# bl_dora2.net
KiCad netlist of a schematic drawn in EAGLE
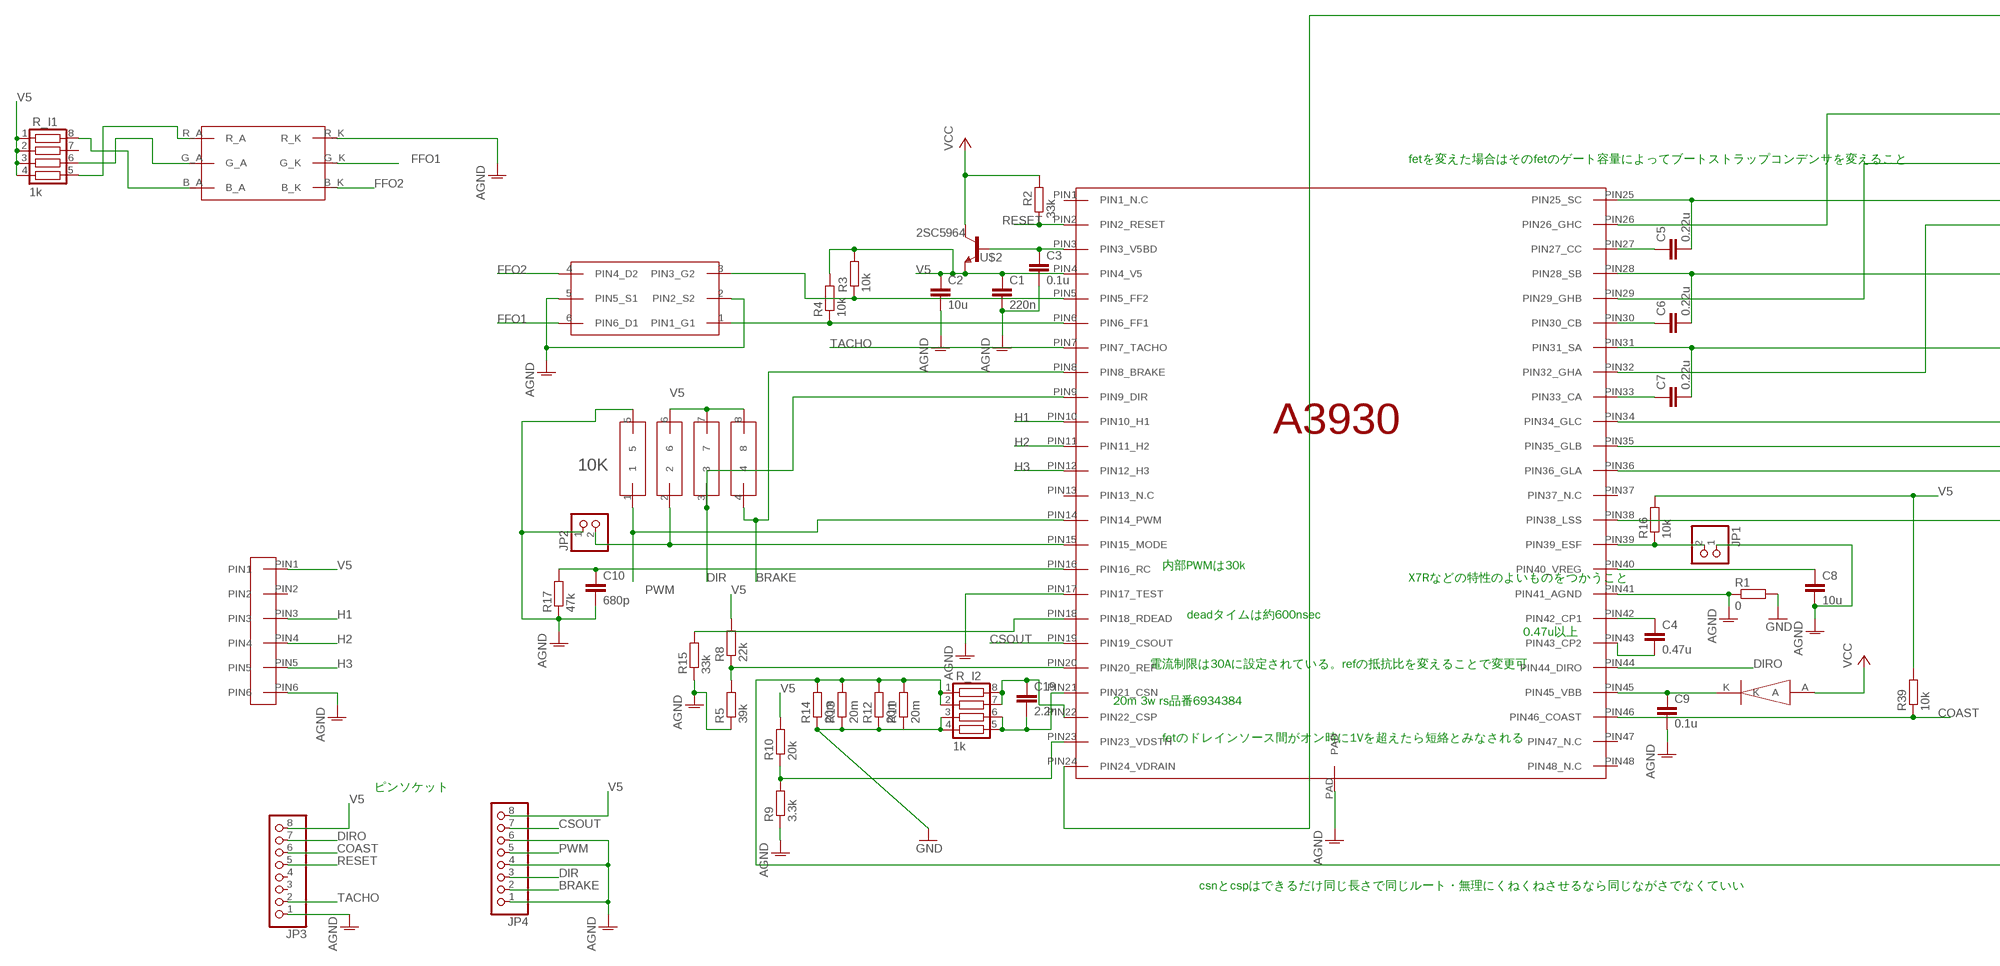
[diagram p0: schematic, sheet 1, part 1 of 2]
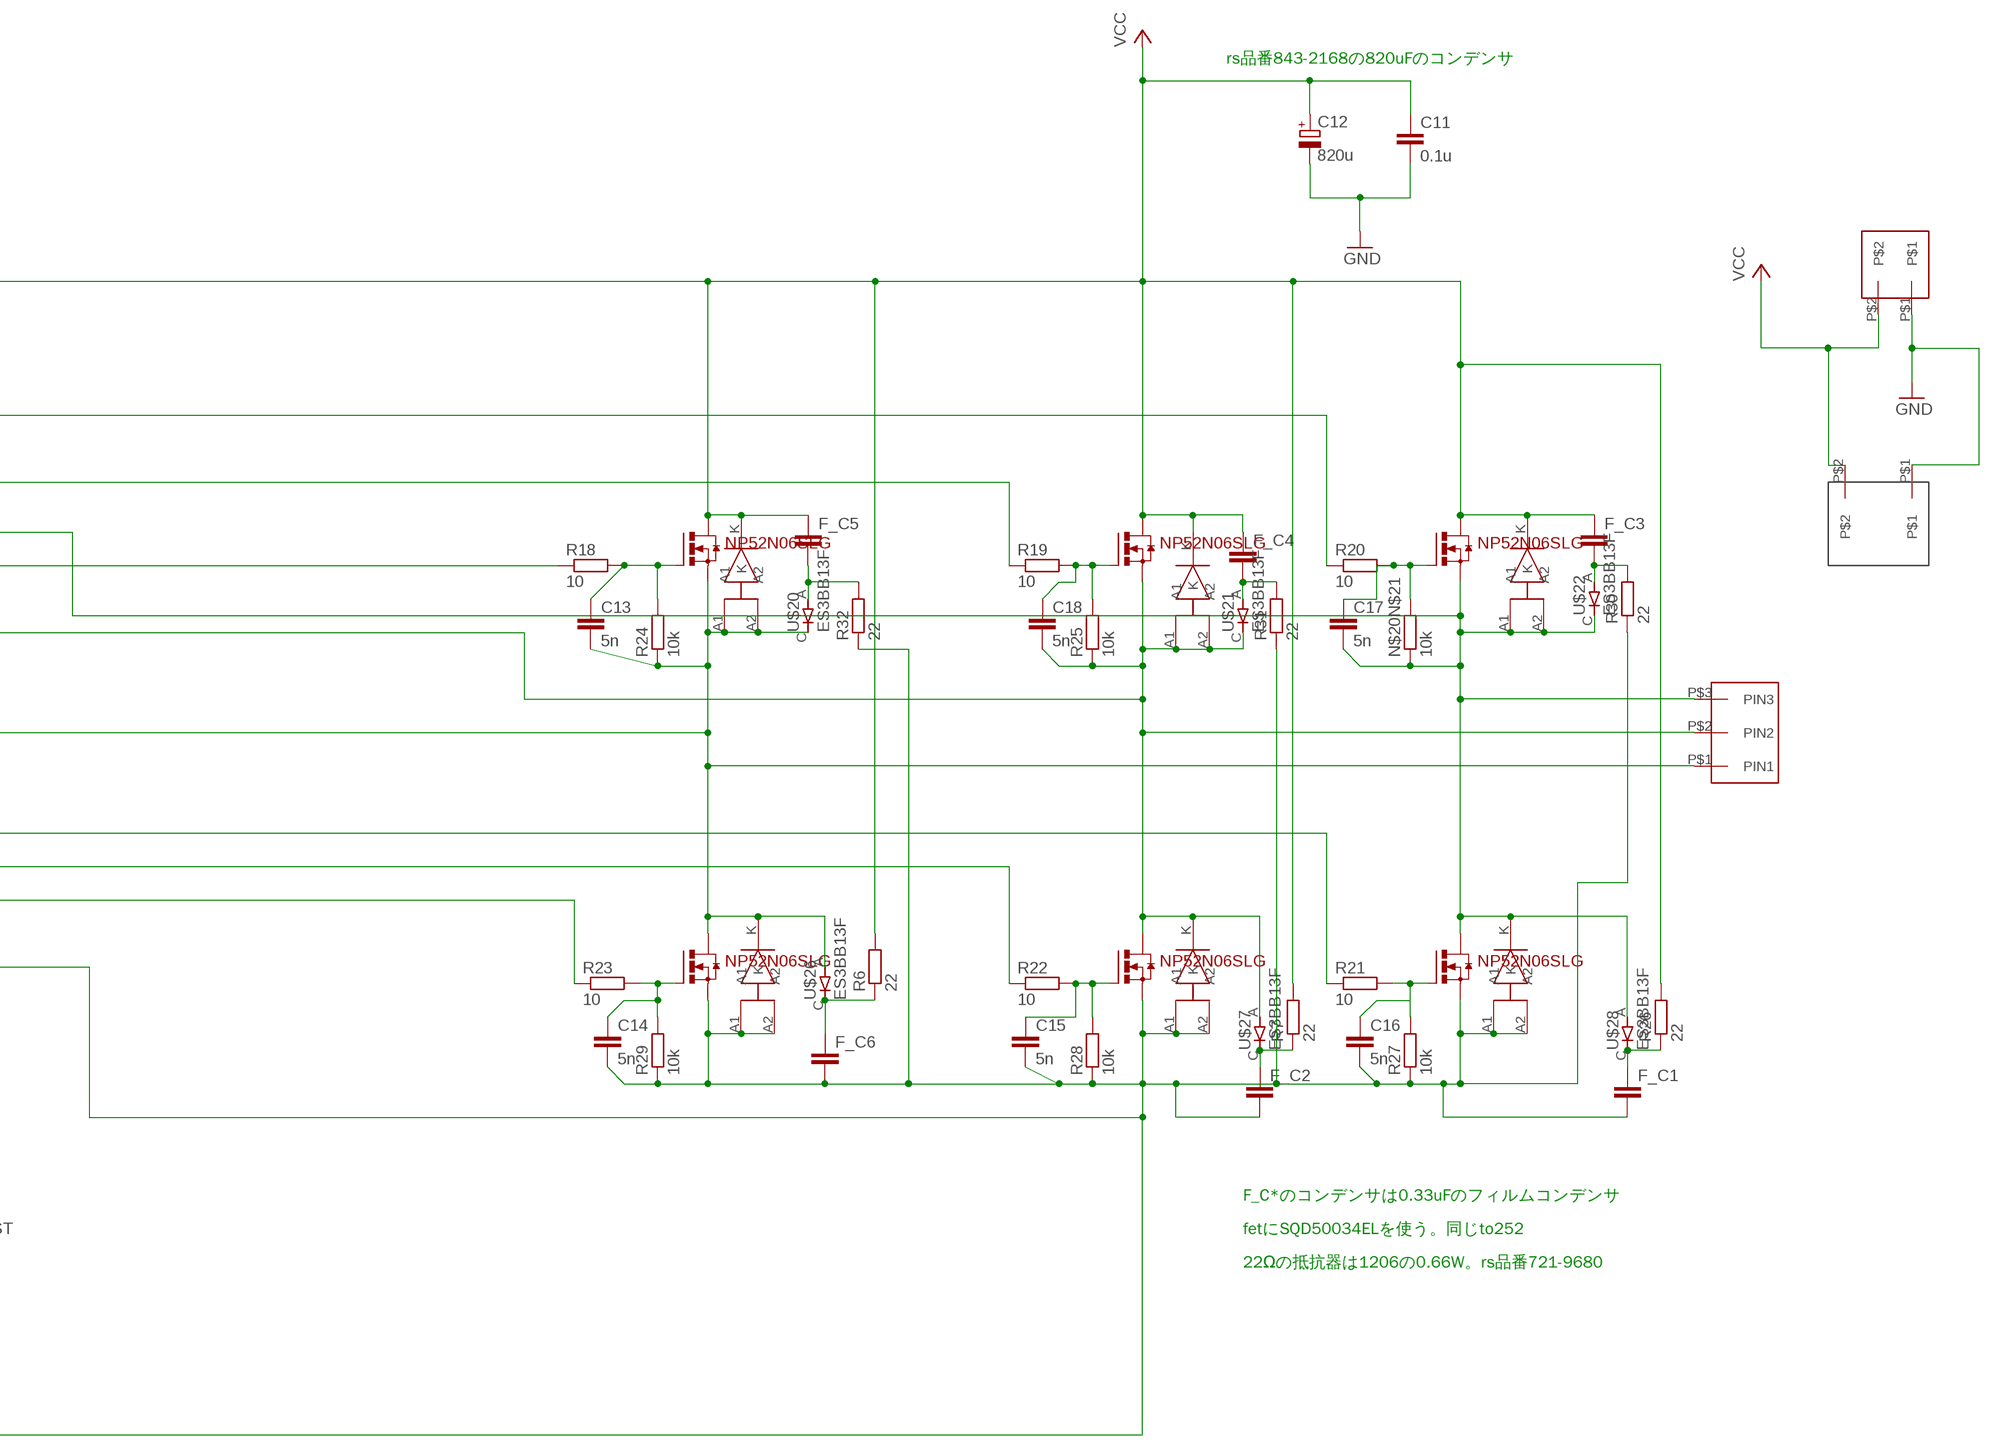
[diagram p1: schematic, sheet 1, part 2 of 2]

(export (version "E")
  (design (tool "Eeschema 10.0.6"))
  (components
    (comp (ref "C1")
      (value "220n")
      (footprint "eagle-import:C2012")
      (libsource (lib "eagle-import") (part "C-EUC2012"))
    )
    (comp (ref "C2")
      (value "10u")
      (footprint "eagle-import:C2012")
      (libsource (lib "eagle-import") (part "C-EUC2012"))
    )
    (comp (ref "C3")
      (value "0.1u")
      (footprint "eagle-import:C2012")
      (libsource (lib "eagle-import") (part "C-EUC2012"))
    )
    (comp (ref "C4")
      (value "0.47u")
      (footprint "eagle-import:C2012")
      (libsource (lib "eagle-import") (part "C-EUC2012"))
    )
    (comp (ref "C5")
      (value "0.22u")
      (footprint "eagle-import:C2012")
      (libsource (lib "eagle-import") (part "C-EUC2012"))
    )
    (comp (ref "C6")
      (value "0.22u")
      (footprint "eagle-import:C2012")
      (libsource (lib "eagle-import") (part "C-EUC2012"))
    )
    (comp (ref "C7")
      (value "0.22u")
      (footprint "eagle-import:C2012")
      (libsource (lib "eagle-import") (part "C-EUC2012"))
    )
    (comp (ref "C8")
      (value "10u")
      (footprint "eagle-import:C2012")
      (libsource (lib "eagle-import") (part "C-EUC2012"))
    )
    (comp (ref "C9")
      (value "0.1u")
      (footprint "eagle-import:C2012")
      (libsource (lib "eagle-import") (part "C-EUC2012"))
    )
    (comp (ref "C10")
      (value "680p")
      (footprint "eagle-import:C2012")
      (libsource (lib "eagle-import") (part "C-EUC2012"))
    )
    (comp (ref "C11")
      (value "0.1u")
      (footprint "eagle-import:C2012")
      (libsource (lib "eagle-import") (part "C-EUC2012"))
    )
    (comp (ref "C12")
      (value "820u")
      (footprint "eagle-import:153CLV-1012")
      (libsource (lib "eagle-import") (part "CPOL-EU153CLV-1012"))
    )
    (comp (ref "C13")
      (value "5n")
      (footprint "eagle-import:C2012")
      (libsource (lib "eagle-import") (part "C-EUC2012"))
    )
    (comp (ref "C14")
      (value "5n")
      (footprint "eagle-import:C2012")
      (libsource (lib "eagle-import") (part "C-EUC2012"))
    )
    (comp (ref "C15")
      (value "5n")
      (footprint "eagle-import:C2012")
      (libsource (lib "eagle-import") (part "C-EUC2012"))
    )
    (comp (ref "C16")
      (value "5n")
      (footprint "eagle-import:C2012")
      (libsource (lib "eagle-import") (part "C-EUC2012"))
    )
    (comp (ref "C17")
      (value "5n")
      (footprint "eagle-import:C2012")
      (libsource (lib "eagle-import") (part "C-EUC2012"))
    )
    (comp (ref "C18")
      (value "5n")
      (footprint "eagle-import:C2012")
      (libsource (lib "eagle-import") (part "C-EUC2012"))
    )
    (comp (ref "C19")
      (value "2.2n")
      (footprint "eagle-import:C1608")
      (libsource (lib "eagle-import") (part "C-EUC1608"))
    )
    (comp (ref "F_C1")
      (value "FIL_CAPA")
      (footprint "eagle-import:FIL_CAPA")
      (libsource (lib "eagle-import") (part "FIL_CAPA"))
    )
    (comp (ref "F_C2")
      (value "FIL_CAPA")
      (footprint "eagle-import:FIL_CAPA")
      (libsource (lib "eagle-import") (part "FIL_CAPA"))
    )
    (comp (ref "F_C3")
      (value "FIL_CAPA")
      (footprint "eagle-import:FIL_CAPA")
      (libsource (lib "eagle-import") (part "FIL_CAPA"))
    )
    (comp (ref "F_C4")
      (value "FIL_CAPA")
      (footprint "eagle-import:FIL_CAPA")
      (libsource (lib "eagle-import") (part "FIL_CAPA"))
    )
    (comp (ref "F_C5")
      (value "FIL_CAPA")
      (footprint "eagle-import:FIL_CAPA")
      (libsource (lib "eagle-import") (part "FIL_CAPA"))
    )
    (comp (ref "F_C6")
      (value "FIL_CAPA")
      (footprint "eagle-import:FIL_CAPA")
      (libsource (lib "eagle-import") (part "FIL_CAPA"))
    )
    (comp (ref "JP1")
      (value "PINHD-1X2")
      (footprint "eagle-import:1X02")
      (libsource (lib "eagle-import") (part "PINHD-1X2"))
    )
    (comp (ref "JP2")
      (value "PINHD-1X2")
      (footprint "eagle-import:1X02")
      (libsource (lib "eagle-import") (part "PINHD-1X2"))
    )
    (comp (ref "JP3")
      (value "PINHD-1X8")
      (footprint "eagle-import:1X08")
      (libsource (lib "eagle-import") (part "PINHD-1X8"))
    )
    (comp (ref "JP4")
      (value "PINHD-1X8")
      (footprint "eagle-import:1X08")
      (libsource (lib "eagle-import") (part "PINHD-1X8"))
    )
    (comp (ref "N$20N$21")
      (value "10k")
      (footprint "eagle-import:M2012")
      (libsource (lib "eagle-import") (part "R-EU_M2012"))
    )
    (comp (ref "R1")
      (value "0")
      (footprint "eagle-import:M2012")
      (libsource (lib "eagle-import") (part "R-EU_M2012"))
    )
    (comp (ref "R2")
      (value "33k")
      (footprint "eagle-import:M2012")
      (libsource (lib "eagle-import") (part "R-EU_M2012"))
    )
    (comp (ref "R3")
      (value "10k")
      (footprint "eagle-import:M2012")
      (libsource (lib "eagle-import") (part "R-EU_M2012"))
    )
    (comp (ref "R4")
      (value "10k")
      (footprint "eagle-import:M2012")
      (libsource (lib "eagle-import") (part "R-EU_M2012"))
    )
    (comp (ref "R5")
      (value "39k")
      (footprint "eagle-import:M2012")
      (libsource (lib "eagle-import") (part "R-EU_M2012"))
    )
    (comp (ref "R6")
      (value "22")
      (footprint "eagle-import:R1206")
      (libsource (lib "eagle-import") (part "R-EU_R1206"))
    )
    (comp (ref "R7")
      (value "22")
      (footprint "eagle-import:R1206")
      (libsource (lib "eagle-import") (part "R-EU_R1206"))
    )
    (comp (ref "R8")
      (value "22k")
      (footprint "eagle-import:M2012")
      (libsource (lib "eagle-import") (part "R-EU_M2012"))
    )
    (comp (ref "R9")
      (value "3.3k")
      (footprint "eagle-import:M2012")
      (libsource (lib "eagle-import") (part "R-EU_M2012"))
    )
    (comp (ref "R10")
      (value "20k")
      (footprint "eagle-import:M2012")
      (libsource (lib "eagle-import") (part "R-EU_M2012"))
    )
    (comp (ref "R11")
      (value "20m")
      (footprint "eagle-import:R2512")
      (libsource (lib "eagle-import") (part "R-EU_R2512"))
    )
    (comp (ref "R12")
      (value "20m")
      (footprint "eagle-import:R2512")
      (libsource (lib "eagle-import") (part "R-EU_R2512"))
    )
    (comp (ref "R13")
      (value "20m")
      (footprint "eagle-import:R2512")
      (libsource (lib "eagle-import") (part "R-EU_R2512"))
    )
    (comp (ref "R14")
      (value "20m")
      (footprint "eagle-import:R2512")
      (libsource (lib "eagle-import") (part "R-EU_R2512"))
    )
    (comp (ref "R15")
      (value "33k")
      (footprint "eagle-import:M2012")
      (libsource (lib "eagle-import") (part "R-EU_M2012"))
    )
    (comp (ref "R16")
      (value "10k")
      (footprint "eagle-import:M2012")
      (libsource (lib "eagle-import") (part "R-EU_M2012"))
    )
    (comp (ref "R17")
      (value "47k")
      (footprint "eagle-import:M2012")
      (libsource (lib "eagle-import") (part "R-EU_M2012"))
    )
    (comp (ref "R18")
      (value "10")
      (footprint "eagle-import:M2012")
      (libsource (lib "eagle-import") (part "R-EU_M2012"))
    )
    (comp (ref "R19")
      (value "10")
      (footprint "eagle-import:M2012")
      (libsource (lib "eagle-import") (part "R-EU_M2012"))
    )
    (comp (ref "R20")
      (value "10")
      (footprint "eagle-import:M2012")
      (libsource (lib "eagle-import") (part "R-EU_M2012"))
    )
    (comp (ref "R21")
      (value "10")
      (footprint "eagle-import:M2012")
      (libsource (lib "eagle-import") (part "R-EU_M2012"))
    )
    (comp (ref "R22")
      (value "10")
      (footprint "eagle-import:M2012")
      (libsource (lib "eagle-import") (part "R-EU_M2012"))
    )
    (comp (ref "R23")
      (value "10")
      (footprint "eagle-import:M2012")
      (libsource (lib "eagle-import") (part "R-EU_M2012"))
    )
    (comp (ref "R24")
      (value "10k")
      (footprint "eagle-import:M2012")
      (libsource (lib "eagle-import") (part "R-EU_M2012"))
    )
    (comp (ref "R25")
      (value "10k")
      (footprint "eagle-import:M2012")
      (libsource (lib "eagle-import") (part "R-EU_M2012"))
    )
    (comp (ref "R26")
      (value "22")
      (footprint "eagle-import:R1206")
      (libsource (lib "eagle-import") (part "R-EU_R1206"))
    )
    (comp (ref "R27")
      (value "10k")
      (footprint "eagle-import:M2012")
      (libsource (lib "eagle-import") (part "R-EU_M2012"))
    )
    (comp (ref "R28")
      (value "10k")
      (footprint "eagle-import:M2012")
      (libsource (lib "eagle-import") (part "R-EU_M2012"))
    )
    (comp (ref "R29")
      (value "10k")
      (footprint "eagle-import:M2012")
      (libsource (lib "eagle-import") (part "R-EU_M2012"))
    )
    (comp (ref "R30")
      (value "22")
      (footprint "eagle-import:R1206")
      (libsource (lib "eagle-import") (part "R-EU_R1206"))
    )
    (comp (ref "R31")
      (value "22")
      (footprint "eagle-import:R1206")
      (libsource (lib "eagle-import") (part "R-EU_R1206"))
    )
    (comp (ref "R32")
      (value "22")
      (footprint "eagle-import:R1206")
      (libsource (lib "eagle-import") (part "R-EU_R1206"))
    )
    (comp (ref "R39")
      (value "10k")
      (footprint "eagle-import:M2012")
      (libsource (lib "eagle-import") (part "R-EU_M2012"))
    )
    (comp (ref "R_I1")
      (value "1k")
      (footprint "eagle-import:0603X4RESISTOR")
      (libsource (lib "eagle-import") (part "0603X4RESISTOR"))
    )
    (comp (ref "R_I2")
      (value "1k")
      (footprint "eagle-import:0603X4RESISTOR")
      (libsource (lib "eagle-import") (part "R_SHUGOU"))
    )
    (comp (ref "U$1")
      (value "A3930")
      (footprint "eagle-import:A3930")
      (libsource (lib "eagle-import") (part "A3930"))
    )
    (comp (ref "U$2")
      (value "2SC5964")
      (footprint "eagle-import:2SC5964")
      (libsource (lib "eagle-import") (part "2SC5964"))
    )
    (comp (ref "U$3")
      (value "SSOT6_FET")
      (footprint "eagle-import:SSOT6_FET")
      (libsource (lib "eagle-import") (part "SSOT6_FET"))
    )
    (comp (ref "U$4")
      (value "RGB_LED")
      (footprint "eagle-import:RGB_LED")
      (libsource (lib "eagle-import") (part "RGB_LED"))
    )
    (comp (ref "U$5")
      (value "10K")
      (footprint "eagle-import:1005X4RESISTOR")
      (libsource (lib "eagle-import") (part "1005X4RESISTOR"))
    )
    (comp (ref "U$6")
      (value "SMD_DAIOD")
      (footprint "eagle-import:SMD_DAIOD")
      (libsource (lib "eagle-import") (part "SMD_DAIOD"))
    )
    (comp (ref "U$7")
      (value "NP52N06SLG")
      (footprint "eagle-import:NP52N06SLG")
      (libsource (lib "eagle-import") (part "NP52N06SLG"))
    )
    (comp (ref "U$8")
      (value "NP52N06SLG")
      (footprint "eagle-import:NP52N06SLG")
      (libsource (lib "eagle-import") (part "NP52N06SLG"))
    )
    (comp (ref "U$9")
      (value "NP52N06SLG")
      (footprint "eagle-import:NP52N06SLG")
      (libsource (lib "eagle-import") (part "NP52N06SLG"))
    )
    (comp (ref "U$10")
      (value "NP52N06SLG")
      (footprint "eagle-import:NP52N06SLG")
      (libsource (lib "eagle-import") (part "NP52N06SLG"))
    )
    (comp (ref "U$11")
      (value "NP52N06SLG")
      (footprint "eagle-import:NP52N06SLG")
      (libsource (lib "eagle-import") (part "NP52N06SLG"))
    )
    (comp (ref "U$12")
      (value "NP52N06SLG")
      (footprint "eagle-import:NP52N06SLG")
      (libsource (lib "eagle-import") (part "NP52N06SLG"))
    )
    (comp (ref "U$13")
      (value "SBR10M100P5Q")
      (footprint "eagle-import:SBR10M100P5Q")
      (libsource (lib "eagle-import") (part "SBR10M100P5Q"))
    )
    (comp (ref "U$14")
      (value "SBR10M100P5Q")
      (footprint "eagle-import:SBR10M100P5Q")
      (libsource (lib "eagle-import") (part "SBR10M100P5Q"))
    )
    (comp (ref "U$15")
      (value "SBR10M100P5Q")
      (footprint "eagle-import:SBR10M100P5Q")
      (libsource (lib "eagle-import") (part "SBR10M100P5Q"))
    )
    (comp (ref "U$16")
      (value "SBR10M100P5Q")
      (footprint "eagle-import:SBR10M100P5Q")
      (libsource (lib "eagle-import") (part "SBR10M100P5Q"))
    )
    (comp (ref "U$17")
      (value "SBR10M100P5Q")
      (footprint "eagle-import:SBR10M100P5Q")
      (libsource (lib "eagle-import") (part "SBR10M100P5Q"))
    )
    (comp (ref "U$18")
      (value "SBR10M100P5Q")
      (footprint "eagle-import:SBR10M100P5Q")
      (libsource (lib "eagle-import") (part "SBR10M100P5Q"))
    )
    (comp (ref "U$19")
      (value "XH_2P")
      (footprint "eagle-import:XH_2P")
      (libsource (lib "eagle-import") (part "XH_2P"))
    )
    (comp (ref "U$20")
      (value "ES3BB13F")
      (footprint "eagle-import:ES3BB13F")
      (libsource (lib "eagle-import") (part "ES3BB13F"))
    )
    (comp (ref "U$21")
      (value "ES3BB13F")
      (footprint "eagle-import:ES3BB13F")
      (libsource (lib "eagle-import") (part "ES3BB13F"))
    )
    (comp (ref "U$22")
      (value "ES3BB13F")
      (footprint "eagle-import:ES3BB13F")
      (libsource (lib "eagle-import") (part "ES3BB13F"))
    )
    (comp (ref "U$23")
      (value "ZH_6P_L")
      (footprint "eagle-import:ZH_6P_L")
      (libsource (lib "eagle-import") (part "ZH_6P_L"))
    )
    (comp (ref "U$24")
      (value "XT60")
      (footprint "eagle-import:XT60")
      (libsource (lib "eagle-import") (part "XT60"))
    )
    (comp (ref "U$25")
      (value "VL_3P")
      (footprint "eagle-import:VL_3P")
      (libsource (lib "eagle-import") (part "VL_3P"))
    )
    (comp (ref "U$26")
      (value "ES3BB13F")
      (footprint "eagle-import:ES3BB13F")
      (libsource (lib "eagle-import") (part "ES3BB13F"))
    )
    (comp (ref "U$27")
      (value "ES3BB13F")
      (footprint "eagle-import:ES3BB13F")
      (libsource (lib "eagle-import") (part "ES3BB13F"))
    )
    (comp (ref "U$28")
      (value "ES3BB13F")
      (footprint "eagle-import:ES3BB13F")
      (libsource (lib "eagle-import") (part "ES3BB13F"))
    )
  )
  (nets
    (net (code "1") (name "/BRAKE") (class "Default")
      (node (ref "JP4") (pin "2") (pinfunction "2_2") (pintype "passive"))
      (node (ref "U$1") (pin "PIN8") (pinfunction "PIN8_BRAKE_PIN8") (pintype "bidirectional"))
      (node (ref "U$5") (pin "4") (pinfunction "4_4") (pintype "bidirectional"))
    )
    (net (code "2") (name "/COAST") (class "Default")
      (node (ref "JP3") (pin "6") (pinfunction "6_6") (pintype "passive"))
      (node (ref "R39") (pin "1") (pinfunction "1_1") (pintype "passive"))
      (node (ref "U$1") (pin "PIN46") (pinfunction "PIN46_COAST_PIN46") (pintype "bidirectional"))
    )
    (net (code "3") (name "/CSOUT") (class "Default")
      (node (ref "JP4") (pin "7") (pinfunction "7_7") (pintype "passive"))
      (node (ref "U$1") (pin "PIN19") (pinfunction "PIN19_CSOUT_PIN19") (pintype "bidirectional"))
    )
    (net (code "4") (name "/DIR") (class "Default")
      (node (ref "JP4") (pin "3") (pinfunction "3_3") (pintype "passive"))
      (node (ref "U$1") (pin "PIN9") (pinfunction "PIN9_DIR_PIN9") (pintype "bidirectional"))
      (node (ref "U$5") (pin "3") (pinfunction "3_3") (pintype "bidirectional"))
    )
    (net (code "5") (name "/DIRO") (class "Default")
      (node (ref "JP3") (pin "7") (pinfunction "7_7") (pintype "passive"))
      (node (ref "U$1") (pin "PIN44") (pinfunction "PIN44_DIRO_PIN44") (pintype "bidirectional"))
    )
    (net (code "6") (name "/FFO1") (class "Default")
      (node (ref "U$3") (pin "6") (pinfunction "PIN6_D1_6") (pintype "bidirectional"))
      (node (ref "U$4") (pin "G_K") (pinfunction "G_K_G_K") (pintype "bidirectional"))
    )
    (net (code "7") (name "/FFO2") (class "Default")
      (node (ref "U$3") (pin "4") (pinfunction "PIN4_D2_4") (pintype "bidirectional"))
      (node (ref "U$4") (pin "B_K") (pinfunction "B_K_B_K") (pintype "bidirectional"))
    )
    (net (code "8") (name "/H1") (class "Default")
      (node (ref "U$1") (pin "PIN10") (pinfunction "PIN10_H1_PIN10") (pintype "bidirectional"))
      (node (ref "U$23") (pin "PIN3") (pinfunction "PIN3_PIN3") (pintype "bidirectional"))
    )
    (net (code "9") (name "/H2") (class "Default")
      (node (ref "U$1") (pin "PIN11") (pinfunction "PIN11_H2_PIN11") (pintype "bidirectional"))
      (node (ref "U$23") (pin "PIN4") (pinfunction "PIN4_PIN4") (pintype "bidirectional"))
    )
    (net (code "10") (name "/H3") (class "Default")
      (node (ref "U$1") (pin "PIN12") (pinfunction "PIN12_H3_PIN12") (pintype "bidirectional"))
      (node (ref "U$23") (pin "PIN5") (pinfunction "PIN5_PIN5") (pintype "bidirectional"))
    )
    (net (code "11") (name "/PWM") (class "Default")
      (node (ref "JP4") (pin "5") (pinfunction "5_5") (pintype "passive"))
      (node (ref "U$1") (pin "PIN14") (pinfunction "PIN14_PWM_PIN14") (pintype "bidirectional"))
      (node (ref "U$5") (pin "1") (pinfunction "1_1") (pintype "bidirectional"))
    )
    (net (code "12") (name "/RESET") (class "Default")
      (node (ref "JP3") (pin "5") (pinfunction "5_5") (pintype "passive"))
      (node (ref "R2") (pin "1") (pinfunction "1_1") (pintype "passive"))
      (node (ref "U$1") (pin "PIN2") (pinfunction "PIN2_RESET_PIN2") (pintype "bidirectional"))
    )
    (net (code "13") (name "/TACHO") (class "Default")
      (node (ref "JP3") (pin "2") (pinfunction "2_2") (pintype "passive"))
      (node (ref "U$1") (pin "PIN7") (pinfunction "PIN7_TACHO_PIN7") (pintype "bidirectional"))
    )
    (net (code "14") (name "/V5") (class "Default")
      (node (ref "C1") (pin "1") (pinfunction "1_1") (pintype "passive"))
      (node (ref "C2") (pin "1") (pinfunction "1_1") (pintype "passive"))
      (node (ref "JP3") (pin "8") (pinfunction "8_8") (pintype "passive"))
      (node (ref "JP4") (pin "8") (pinfunction "8_8") (pintype "passive"))
      (node (ref "R10") (pin "2") (pinfunction "2_2") (pintype "passive"))
      (node (ref "R16") (pin "2") (pinfunction "2_2") (pintype "passive"))
      (node (ref "R3") (pin "2") (pinfunction "2_2") (pintype "passive"))
      (node (ref "R39") (pin "2") (pinfunction "2_2") (pintype "passive"))
      (node (ref "R4") (pin "2") (pinfunction "2_2") (pintype "passive"))
      (node (ref "R8") (pin "2") (pinfunction "2_2") (pintype "passive"))
      (node (ref "R_I1") (pin "1") (pinfunction "1_1") (pintype "passive"))
      (node (ref "R_I1") (pin "2") (pinfunction "2_2") (pintype "passive"))
      (node (ref "R_I1") (pin "3") (pinfunction "3_3") (pintype "passive"))
      (node (ref "R_I1") (pin "4") (pinfunction "4_4") (pintype "passive"))
      (node (ref "U$1") (pin "PIN4") (pinfunction "PIN4_V5_PIN4") (pintype "bidirectional"))
      (node (ref "U$2") (pin "E") (pinfunction "E_E") (pintype "passive"))
      (node (ref "U$23") (pin "PIN1") (pinfunction "PIN1_PIN1") (pintype "bidirectional"))
      (node (ref "U$5") (pin "6") (pinfunction "6_6") (pintype "bidirectional"))
      (node (ref "U$5") (pin "7") (pinfunction "7_7") (pintype "bidirectional"))
      (node (ref "U$5") (pin "8") (pinfunction "8_8") (pintype "bidirectional"))
    )
    (net (code "15") (name "AGND") (class "Default")
      (node (ref "C1") (pin "2") (pinfunction "2_2") (pintype "passive"))
      (node (ref "C10") (pin "2") (pinfunction "2_2") (pintype "passive"))
      (node (ref "C2") (pin "2") (pinfunction "2_2") (pintype "passive"))
      (node (ref "C3") (pin "2") (pinfunction "2_2") (pintype "passive"))
      (node (ref "C8") (pin "2") (pinfunction "2_2") (pintype "passive"))
      (node (ref "C9") (pin "2") (pinfunction "2_2") (pintype "passive"))
      (node (ref "JP1") (pin "1") (pinfunction "1_1") (pintype "passive"))
      (node (ref "JP2") (pin "1") (pinfunction "1_1") (pintype "passive"))
      (node (ref "JP3") (pin "1") (pinfunction "1_1") (pintype "passive"))
      (node (ref "JP4") (pin "1") (pinfunction "1_1") (pintype "passive"))
      (node (ref "JP4") (pin "4") (pinfunction "4_4") (pintype "passive"))
      (node (ref "JP4") (pin "6") (pinfunction "6_6") (pintype "passive"))
      (node (ref "R1") (pin "1") (pinfunction "1_1") (pintype "passive"))
      (node (ref "R15") (pin "1") (pinfunction "1_1") (pintype "passive"))
      (node (ref "R17") (pin "1") (pinfunction "1_1") (pintype "passive"))
      (node (ref "R5") (pin "1") (pinfunction "1_1") (pintype "passive"))
      (node (ref "R9") (pin "1") (pinfunction "1_1") (pintype "passive"))
      (node (ref "U$1") (pin "PAD") (pinfunction "PAD_PAD") (pintype "bidirectional"))
      (node (ref "U$1") (pin "PIN17") (pinfunction "PIN17_TEST_PIN17") (pintype "bidirectional"))
      (node (ref "U$1") (pin "PIN41") (pinfunction "PIN41_AGND_PIN41") (pintype "bidirectional"))
      (node (ref "U$23") (pin "PIN6") (pinfunction "PIN6_PIN6") (pintype "bidirectional"))
      (node (ref "U$3") (pin "2") (pinfunction "PIN2_S2_2") (pintype "bidirectional"))
      (node (ref "U$3") (pin "5") (pinfunction "PIN5_S1_5") (pintype "bidirectional"))
      (node (ref "U$4") (pin "R_K") (pinfunction "R_K_R_K") (pintype "bidirectional"))
      (node (ref "U$5") (pin "5") (pinfunction "5_5") (pintype "bidirectional"))
    )
    (net (code "16") (name "GND") (class "Default")
      (node (ref "C11") (pin "2") (pinfunction "2_2") (pintype "passive"))
      (node (ref "C12") (pin "-") (pinfunction "-_-") (pintype "passive"))
      (node (ref "R1") (pin "2") (pinfunction "2_2") (pintype "passive"))
      (node (ref "R11") (pin "1") (pinfunction "1_1") (pintype "passive"))
      (node (ref "R12") (pin "1") (pinfunction "1_1") (pintype "passive"))
      (node (ref "R13") (pin "1") (pinfunction "1_1") (pintype "passive"))
      (node (ref "R14") (pin "1") (pinfunction "1_1") (pintype "passive"))
      (node (ref "R_I2") (pin "3") (pinfunction "3_3") (pintype "passive"))
      (node (ref "R_I2") (pin "4") (pinfunction "4_4") (pintype "passive"))
      (node (ref "U$19") (pin "P$1") (pinfunction "P$1_P$1") (pintype "bidirectional"))
      (node (ref "U$24") (pin "P$1") (pinfunction "P$1_P$1") (pintype "bidirectional"))
    )
    (net (code "17") (name "Net-(C13-Pad1)") (class "Default")
      (node (ref "C13") (pin "1") (pinfunction "1_1") (pintype "passive"))
      (node (ref "R18") (pin "2") (pinfunction "2_2") (pintype "passive"))
      (node (ref "R24") (pin "2") (pinfunction "2_2") (pintype "passive"))
      (node (ref "U$7") (pin "PIN1_G") (pinfunction "PIN1_G_PIN1_G") (pintype "passive"))
    )
    (net (code "18") (name "Net-(C14-Pad1)") (class "Default")
      (node (ref "C14") (pin "1") (pinfunction "1_1") (pintype "passive"))
      (node (ref "R23") (pin "2") (pinfunction "2_2") (pintype "passive"))
      (node (ref "R29") (pin "2") (pinfunction "2_2") (pintype "passive"))
      (node (ref "U$8") (pin "PIN1_G") (pinfunction "PIN1_G_PIN1_G") (pintype "passive"))
    )
    (net (code "19") (name "Net-(C15-Pad1)") (class "Default")
      (node (ref "C15") (pin "1") (pinfunction "1_1") (pintype "passive"))
      (node (ref "R22") (pin "2") (pinfunction "2_2") (pintype "passive"))
      (node (ref "R28") (pin "2") (pinfunction "2_2") (pintype "passive"))
      (node (ref "U$10") (pin "PIN1_G") (pinfunction "PIN1_G_PIN1_G") (pintype "passive"))
    )
    (net (code "20") (name "Net-(C16-Pad1)") (class "Default")
      (node (ref "C16") (pin "1") (pinfunction "1_1") (pintype "passive"))
      (node (ref "R21") (pin "2") (pinfunction "2_2") (pintype "passive"))
      (node (ref "R27") (pin "2") (pinfunction "2_2") (pintype "passive"))
      (node (ref "U$12") (pin "PIN1_G") (pinfunction "PIN1_G_PIN1_G") (pintype "passive"))
    )
    (net (code "21") (name "Net-(C17-Pad1)") (class "Default")
      (node (ref "C17") (pin "1") (pinfunction "1_1") (pintype "passive"))
      (node (ref "N$20N$21") (pin "2") (pinfunction "2_2") (pintype "passive"))
      (node (ref "R20") (pin "2") (pinfunction "2_2") (pintype "passive"))
      (node (ref "U$11") (pin "PIN1_G") (pinfunction "PIN1_G_PIN1_G") (pintype "passive"))
    )
    (net (code "22") (name "Net-(C18-Pad1)") (class "Default")
      (node (ref "C18") (pin "1") (pinfunction "1_1") (pintype "passive"))
      (node (ref "R19") (pin "2") (pinfunction "2_2") (pintype "passive"))
      (node (ref "R25") (pin "2") (pinfunction "2_2") (pintype "passive"))
      (node (ref "U$9") (pin "PIN1_G") (pinfunction "PIN1_G_PIN1_G") (pintype "passive"))
    )
    (net (code "23") (name "Net-(F_C1-1)") (class "Default")
      (node (ref "F_C1") (pin "P$1") (pinfunction "1_P$1") (pintype "passive"))
      (node (ref "R26") (pin "1") (pinfunction "1_1") (pintype "passive"))
      (node (ref "U$28") (pin "C") (pinfunction "C_C") (pintype "passive"))
    )
    (net (code "24") (name "Net-(F_C1-2)") (class "Default")
      (node (ref "C14") (pin "2") (pinfunction "2_2") (pintype "passive"))
      (node (ref "C15") (pin "2") (pinfunction "2_2") (pintype "passive"))
      (node (ref "C16") (pin "2") (pinfunction "2_2") (pintype "passive"))
      (node (ref "F_C1") (pin "P$2") (pinfunction "2_P$2") (pintype "passive"))
      (node (ref "F_C2") (pin "P$2") (pinfunction "2_P$2") (pintype "passive"))
      (node (ref "F_C6") (pin "P$2") (pinfunction "2_P$2") (pintype "passive"))
      (node (ref "R11") (pin "2") (pinfunction "2_2") (pintype "passive"))
      (node (ref "R12") (pin "2") (pinfunction "2_2") (pintype "passive"))
      (node (ref "R13") (pin "2") (pinfunction "2_2") (pintype "passive"))
      (node (ref "R14") (pin "2") (pinfunction "2_2") (pintype "passive"))
      (node (ref "R27") (pin "1") (pinfunction "1_1") (pintype "passive"))
      (node (ref "R28") (pin "1") (pinfunction "1_1") (pintype "passive"))
      (node (ref "R29") (pin "1") (pinfunction "1_1") (pintype "passive"))
      (node (ref "R30") (pin "1") (pinfunction "1_1") (pintype "passive"))
      (node (ref "R31") (pin "1") (pinfunction "1_1") (pintype "passive"))
      (node (ref "R32") (pin "1") (pinfunction "1_1") (pintype "passive"))
      (node (ref "R_I2") (pin "1") (pinfunction "1_1") (pintype "passive"))
      (node (ref "R_I2") (pin "2") (pinfunction "2_2") (pintype "passive"))
      (node (ref "U$1") (pin "PIN38") (pinfunction "PIN38_LSS_PIN38") (pintype "bidirectional"))
      (node (ref "U$10") (pin "PIN3_S") (pinfunction "PIN3_S_PIN3_S") (pintype "passive"))
      (node (ref "U$12") (pin "PIN3_S") (pinfunction "PIN3_S_PIN3_S") (pintype "passive"))
      (node (ref "U$14") (pin "A1") (pinfunction "A1_A1") (pintype "bidirectional"))
      (node (ref "U$14") (pin "A2") (pinfunction "A2_A2") (pintype "bidirectional"))
      (node (ref "U$15") (pin "A1") (pinfunction "A1_A1") (pintype "bidirectional"))
      (node (ref "U$15") (pin "A2") (pinfunction "A2_A2") (pintype "bidirectional"))
      (node (ref "U$18") (pin "A1") (pinfunction "A1_A1") (pintype "bidirectional"))
      (node (ref "U$18") (pin "A2") (pinfunction "A2_A2") (pintype "bidirectional"))
      (node (ref "U$8") (pin "PIN3_S") (pinfunction "PIN3_S_PIN3_S") (pintype "passive"))
    )
    (net (code "25") (name "Net-(F_C2-1)") (class "Default")
      (node (ref "F_C2") (pin "P$1") (pinfunction "1_P$1") (pintype "passive"))
      (node (ref "R7") (pin "1") (pinfunction "1_1") (pintype "passive"))
      (node (ref "U$27") (pin "C") (pinfunction "C_C") (pintype "passive"))
    )
    (net (code "26") (name "Net-(F_C3-2)") (class "Default")
      (node (ref "F_C3") (pin "P$2") (pinfunction "2_P$2") (pintype "passive"))
      (node (ref "R30") (pin "2") (pinfunction "2_2") (pintype "passive"))
      (node (ref "U$22") (pin "A") (pinfunction "A_A") (pintype "passive"))
    )
    (net (code "27") (name "Net-(F_C4-2)") (class "Default")
      (node (ref "F_C4") (pin "P$2") (pinfunction "2_P$2") (pintype "passive"))
      (node (ref "R31") (pin "2") (pinfunction "2_2") (pintype "passive"))
      (node (ref "U$21") (pin "A") (pinfunction "A_A") (pintype "passive"))
    )
    (net (code "28") (name "Net-(F_C5-2)") (class "Default")
      (node (ref "F_C5") (pin "P$2") (pinfunction "2_P$2") (pintype "passive"))
      (node (ref "R32") (pin "2") (pinfunction "2_2") (pintype "passive"))
      (node (ref "U$20") (pin "A") (pinfunction "A_A") (pintype "passive"))
    )
    (net (code "29") (name "Net-(F_C6-1)") (class "Default")
      (node (ref "F_C6") (pin "P$1") (pinfunction "1_P$1") (pintype "passive"))
      (node (ref "R6") (pin "1") (pinfunction "1_1") (pintype "passive"))
      (node (ref "U$26") (pin "C") (pinfunction "C_C") (pintype "passive"))
    )
    (net (code "30") (name "Net-(R_I1-Pad5)") (class "Default")
      (node (ref "R_I1") (pin "5") (pinfunction "5_5") (pintype "passive"))
      (node (ref "U$4") (pin "R_A") (pinfunction "R_A_R_A") (pintype "bidirectional"))
    )
    (net (code "31") (name "Net-(R_I1-Pad6)") (class "Default")
      (node (ref "R_I1") (pin "6") (pinfunction "6_6") (pintype "passive"))
      (node (ref "U$4") (pin "G_A") (pinfunction "G_A_G_A") (pintype "bidirectional"))
    )
    (net (code "32") (name "Net-(R_I1-Pad8)") (class "Default")
      (node (ref "R_I1") (pin "8") (pinfunction "8_8") (pintype "passive"))
      (node (ref "U$4") (pin "B_A") (pinfunction "B_A_B_A") (pintype "bidirectional"))
    )
    (net (code "33") (name "Net-(U$1-PIN3_V5BD)") (class "Default")
      (node (ref "C3") (pin "1") (pinfunction "1_1") (pintype "passive"))
      (node (ref "U$1") (pin "PIN3") (pinfunction "PIN3_V5BD_PIN3") (pintype "bidirectional"))
      (node (ref "U$2") (pin "B") (pinfunction "B_B") (pintype "passive"))
    )
    (net (code "34") (name "Net-(U$1-PIN5_FF2)") (class "Default")
      (node (ref "R3") (pin "1") (pinfunction "1_1") (pintype "passive"))
      (node (ref "U$1") (pin "PIN5") (pinfunction "PIN5_FF2_PIN5") (pintype "bidirectional"))
      (node (ref "U$3") (pin "3") (pinfunction "PIN3_G2_3") (pintype "bidirectional"))
    )
    (net (code "35") (name "Net-(U$1-PIN6_FF1)") (class "Default")
      (node (ref "R4") (pin "1") (pinfunction "1_1") (pintype "passive"))
      (node (ref "U$1") (pin "PIN6") (pinfunction "PIN6_FF1_PIN6") (pintype "bidirectional"))
      (node (ref "U$3") (pin "1") (pinfunction "PIN1_G1_1") (pintype "bidirectional"))
    )
    (net (code "36") (name "Net-(U$1-PIN15_MODE)") (class "Default")
      (node (ref "JP2") (pin "2") (pinfunction "2_2") (pintype "passive"))
      (node (ref "U$1") (pin "PIN15") (pinfunction "PIN15_MODE_PIN15") (pintype "bidirectional"))
      (node (ref "U$5") (pin "2") (pinfunction "2_2") (pintype "bidirectional"))
    )
    (net (code "37") (name "Net-(U$1-PIN16_RC)") (class "Default")
      (node (ref "C10") (pin "1") (pinfunction "1_1") (pintype "passive"))
      (node (ref "R17") (pin "2") (pinfunction "2_2") (pintype "passive"))
      (node (ref "U$1") (pin "PIN16") (pinfunction "PIN16_RC_PIN16") (pintype "bidirectional"))
    )
    (net (code "38") (name "Net-(U$1-PIN18_RDEAD)") (class "Default")
      (node (ref "R15") (pin "2") (pinfunction "2_2") (pintype "passive"))
      (node (ref "U$1") (pin "PIN18") (pinfunction "PIN18_RDEAD_PIN18") (pintype "bidirectional"))
    )
    (net (code "39") (name "Net-(U$1-PIN20_REF)") (class "Default")
      (node (ref "R5") (pin "2") (pinfunction "2_2") (pintype "passive"))
      (node (ref "R8") (pin "1") (pinfunction "1_1") (pintype "passive"))
      (node (ref "U$1") (pin "PIN20") (pinfunction "PIN20_REF_PIN20") (pintype "bidirectional"))
    )
    (net (code "40") (name "Net-(U$1-PIN21_CSN)") (class "Default")
      (node (ref "C19") (pin "2") (pinfunction "2_2") (pintype "passive"))
      (node (ref "R_I2") (pin "5") (pinfunction "5_5") (pintype "passive"))
      (node (ref "R_I2") (pin "6") (pinfunction "6_6") (pintype "passive"))
      (node (ref "U$1") (pin "PIN21") (pinfunction "PIN21_CSN_PIN21") (pintype "bidirectional"))
    )
    (net (code "41") (name "Net-(U$1-PIN22_CSP)") (class "Default")
      (node (ref "C19") (pin "1") (pinfunction "1_1") (pintype "passive"))
      (node (ref "R_I2") (pin "7") (pinfunction "7_7") (pintype "passive"))
      (node (ref "R_I2") (pin "8") (pinfunction "8_8") (pintype "passive"))
      (node (ref "U$1") (pin "PIN22") (pinfunction "PIN22_CSP_PIN22") (pintype "bidirectional"))
    )
    (net (code "42") (name "Net-(U$1-PIN23_VDSTH)") (class "Default")
      (node (ref "R10") (pin "1") (pinfunction "1_1") (pintype "passive"))
      (node (ref "R9") (pin "2") (pinfunction "2_2") (pintype "passive"))
      (node (ref "U$1") (pin "PIN23") (pinfunction "PIN23_VDSTH_PIN23") (pintype "bidirectional"))
    )
    (net (code "43") (name "Net-(U$1-PIN25_SC)") (class "Default")
      (node (ref "C17") (pin "2") (pinfunction "2_2") (pintype "passive"))
      (node (ref "C5") (pin "2") (pinfunction "2_2") (pintype "passive"))
      (node (ref "N$20N$21") (pin "1") (pinfunction "1_1") (pintype "passive"))
      (node (ref "U$1") (pin "PIN25") (pinfunction "PIN25_SC_PIN25") (pintype "bidirectional"))
      (node (ref "U$11") (pin "PIN3_S") (pinfunction "PIN3_S_PIN3_S") (pintype "passive"))
      (node (ref "U$12") (pin "PIN2_D") (pinfunction "PIN2_D_PIN2_D") (pintype "passive"))
      (node (ref "U$17") (pin "A1") (pinfunction "A1_A1") (pintype "bidirectional"))
      (node (ref "U$17") (pin "A2") (pinfunction "A2_A2") (pintype "bidirectional"))
      (node (ref "U$18") (pin "K") (pinfunction "K_K") (pintype "bidirectional"))
      (node (ref "U$22") (pin "C") (pinfunction "C_C") (pintype "passive"))
      (node (ref "U$25") (pin "P$3") (pinfunction "PIN3_P$3") (pintype "bidirectional"))
      (node (ref "U$28") (pin "A") (pinfunction "A_A") (pintype "passive"))
    )
    (net (code "44") (name "Net-(U$1-PIN26_GHC)") (class "Default")
      (node (ref "R20") (pin "1") (pinfunction "1_1") (pintype "passive"))
      (node (ref "U$1") (pin "PIN26") (pinfunction "PIN26_GHC_PIN26") (pintype "bidirectional"))
    )
    (net (code "45") (name "Net-(U$1-PIN27_CC)") (class "Default")
      (node (ref "C5") (pin "1") (pinfunction "1_1") (pintype "passive"))
      (node (ref "U$1") (pin "PIN27") (pinfunction "PIN27_CC_PIN27") (pintype "bidirectional"))
    )
    (net (code "46") (name "Net-(U$1-PIN28_SB)") (class "Default")
      (node (ref "C18") (pin "2") (pinfunction "2_2") (pintype "passive"))
      (node (ref "C6") (pin "2") (pinfunction "2_2") (pintype "passive"))
      (node (ref "R25") (pin "1") (pinfunction "1_1") (pintype "passive"))
      (node (ref "U$1") (pin "PIN28") (pinfunction "PIN28_SB_PIN28") (pintype "bidirectional"))
      (node (ref "U$10") (pin "PIN2_D") (pinfunction "PIN2_D_PIN2_D") (pintype "passive"))
      (node (ref "U$15") (pin "K") (pinfunction "K_K") (pintype "bidirectional"))
      (node (ref "U$16") (pin "A1") (pinfunction "A1_A1") (pintype "bidirectional"))
      (node (ref "U$16") (pin "A2") (pinfunction "A2_A2") (pintype "bidirectional"))
      (node (ref "U$21") (pin "C") (pinfunction "C_C") (pintype "passive"))
      (node (ref "U$25") (pin "P$2") (pinfunction "PIN2_P$2") (pintype "bidirectional"))
      (node (ref "U$27") (pin "A") (pinfunction "A_A") (pintype "passive"))
      (node (ref "U$9") (pin "PIN3_S") (pinfunction "PIN3_S_PIN3_S") (pintype "passive"))
    )
    (net (code "47") (name "Net-(U$1-PIN29_GHB)") (class "Default")
      (node (ref "R19") (pin "1") (pinfunction "1_1") (pintype "passive"))
      (node (ref "U$1") (pin "PIN29") (pinfunction "PIN29_GHB_PIN29") (pintype "bidirectional"))
    )
    (net (code "48") (name "Net-(U$1-PIN30_CB)") (class "Default")
      (node (ref "C6") (pin "1") (pinfunction "1_1") (pintype "passive"))
      (node (ref "U$1") (pin "PIN30") (pinfunction "PIN30_CB_PIN30") (pintype "bidirectional"))
    )
    (net (code "49") (name "Net-(U$1-PIN31_SA)") (class "Default")
      (node (ref "C13") (pin "2") (pinfunction "2_2") (pintype "passive"))
      (node (ref "C7") (pin "2") (pinfunction "2_2") (pintype "passive"))
      (node (ref "R24") (pin "1") (pinfunction "1_1") (pintype "passive"))
      (node (ref "U$1") (pin "PIN31") (pinfunction "PIN31_SA_PIN31") (pintype "bidirectional"))
      (node (ref "U$13") (pin "A1") (pinfunction "A1_A1") (pintype "bidirectional"))
      (node (ref "U$13") (pin "A2") (pinfunction "A2_A2") (pintype "bidirectional"))
      (node (ref "U$14") (pin "K") (pinfunction "K_K") (pintype "bidirectional"))
      (node (ref "U$20") (pin "C") (pinfunction "C_C") (pintype "passive"))
      (node (ref "U$25") (pin "P$1") (pinfunction "PIN1_P$1") (pintype "bidirectional"))
      (node (ref "U$26") (pin "A") (pinfunction "A_A") (pintype "passive"))
      (node (ref "U$7") (pin "PIN3_S") (pinfunction "PIN3_S_PIN3_S") (pintype "passive"))
      (node (ref "U$8") (pin "PIN2_D") (pinfunction "PIN2_D_PIN2_D") (pintype "passive"))
    )
    (net (code "50") (name "Net-(U$1-PIN32_GHA)") (class "Default")
      (node (ref "R18") (pin "1") (pinfunction "1_1") (pintype "passive"))
      (node (ref "U$1") (pin "PIN32") (pinfunction "PIN32_GHA_PIN32") (pintype "bidirectional"))
    )
    (net (code "51") (name "Net-(U$1-PIN33_CA)") (class "Default")
      (node (ref "C7") (pin "1") (pinfunction "1_1") (pintype "passive"))
      (node (ref "U$1") (pin "PIN33") (pinfunction "PIN33_CA_PIN33") (pintype "bidirectional"))
    )
    (net (code "52") (name "Net-(U$1-PIN34_GLC)") (class "Default")
      (node (ref "R21") (pin "1") (pinfunction "1_1") (pintype "passive"))
      (node (ref "U$1") (pin "PIN34") (pinfunction "PIN34_GLC_PIN34") (pintype "bidirectional"))
    )
    (net (code "53") (name "Net-(U$1-PIN35_GLB)") (class "Default")
      (node (ref "R22") (pin "1") (pinfunction "1_1") (pintype "passive"))
      (node (ref "U$1") (pin "PIN35") (pinfunction "PIN35_GLB_PIN35") (pintype "bidirectional"))
    )
    (net (code "54") (name "Net-(U$1-PIN36_GLA)") (class "Default")
      (node (ref "R23") (pin "1") (pinfunction "1_1") (pintype "passive"))
      (node (ref "U$1") (pin "PIN36") (pinfunction "PIN36_GLA_PIN36") (pintype "bidirectional"))
    )
    (net (code "55") (name "Net-(U$1-PIN39_ESF)") (class "Default")
      (node (ref "JP1") (pin "2") (pinfunction "2_2") (pintype "passive"))
      (node (ref "R16") (pin "1") (pinfunction "1_1") (pintype "passive"))
      (node (ref "U$1") (pin "PIN39") (pinfunction "PIN39_ESF_PIN39") (pintype "bidirectional"))
    )
    (net (code "56") (name "Net-(U$1-PIN40_VREG)") (class "Default")
      (node (ref "C8") (pin "1") (pinfunction "1_1") (pintype "passive"))
      (node (ref "U$1") (pin "PIN40") (pinfunction "PIN40_VREG_PIN40") (pintype "bidirectional"))
    )
    (net (code "57") (name "Net-(U$1-PIN42_CP1)") (class "Default")
      (node (ref "C4") (pin "1") (pinfunction "1_1") (pintype "passive"))
      (node (ref "U$1") (pin "PIN42") (pinfunction "PIN42_CP1_PIN42") (pintype "bidirectional"))
    )
    (net (code "58") (name "Net-(U$1-PIN43_CP2)") (class "Default")
      (node (ref "C4") (pin "2") (pinfunction "2_2") (pintype "passive"))
      (node (ref "U$1") (pin "PIN43") (pinfunction "PIN43_CP2_PIN43") (pintype "bidirectional"))
    )
    (net (code "59") (name "Net-(U$1-PIN45_VBB)") (class "Default")
      (node (ref "C9") (pin "1") (pinfunction "1_1") (pintype "passive"))
      (node (ref "U$1") (pin "PIN45") (pinfunction "PIN45_VBB_PIN45") (pintype "bidirectional"))
      (node (ref "U$6") (pin "K") (pinfunction "K_K") (pintype "bidirectional"))
    )
    (net (code "60") (name "VCC") (class "Default")
      (node (ref "C11") (pin "1") (pinfunction "1_1") (pintype "passive"))
      (node (ref "C12") (pin "+") (pinfunction "+_+") (pintype "passive"))
      (node (ref "F_C3") (pin "P$1") (pinfunction "1_P$1") (pintype "passive"))
      (node (ref "F_C4") (pin "P$1") (pinfunction "1_P$1") (pintype "passive"))
      (node (ref "F_C5") (pin "P$1") (pinfunction "1_P$1") (pintype "passive"))
      (node (ref "R2") (pin "2") (pinfunction "2_2") (pintype "passive"))
      (node (ref "R26") (pin "2") (pinfunction "2_2") (pintype "passive"))
      (node (ref "R6") (pin "2") (pinfunction "2_2") (pintype "passive"))
      (node (ref "R7") (pin "2") (pinfunction "2_2") (pintype "passive"))
      (node (ref "U$1") (pin "PIN24") (pinfunction "PIN24_VDRAIN_PIN24") (pintype "bidirectional"))
      (node (ref "U$11") (pin "PIN2_D") (pinfunction "PIN2_D_PIN2_D") (pintype "passive"))
      (node (ref "U$13") (pin "K") (pinfunction "K_K") (pintype "bidirectional"))
      (node (ref "U$16") (pin "K") (pinfunction "K_K") (pintype "bidirectional"))
      (node (ref "U$17") (pin "K") (pinfunction "K_K") (pintype "bidirectional"))
      (node (ref "U$19") (pin "P$2") (pinfunction "P$2_P$2") (pintype "bidirectional"))
      (node (ref "U$2") (pin "C") (pinfunction "C_C") (pintype "passive"))
      (node (ref "U$2") (pin "C@2") (pinfunction "C_C@2") (pintype "passive"))
      (node (ref "U$24") (pin "P$2") (pinfunction "P$2_P$2") (pintype "bidirectional"))
      (node (ref "U$6") (pin "A") (pinfunction "A_A") (pintype "bidirectional"))
      (node (ref "U$7") (pin "PIN2_D") (pinfunction "PIN2_D_PIN2_D") (pintype "passive"))
      (node (ref "U$9") (pin "PIN2_D") (pinfunction "PIN2_D_PIN2_D") (pintype "passive"))
    )
    (net (code "61") (name "unconnected-(JP3-Pad3)") (class "Default")
      (node (ref "JP3") (pin "3") (pinfunction "3_3") (pintype "passive"))
    )
    (net (code "62") (name "unconnected-(JP3-Pad4)") (class "Default")
      (node (ref "JP3") (pin "4") (pinfunction "4_4") (pintype "passive"))
    )
    (net (code "63") (name "unconnected-(R_I1-Pad7)") (class "Default")
      (node (ref "R_I1") (pin "7") (pinfunction "7_7") (pintype "passive"))
    )
    (net (code "64") (name "unconnected-(U$1-PIN1_N.C-PadPIN1)") (class "Default")
      (node (ref "U$1") (pin "PIN1") (pinfunction "PIN1_N.C_PIN1") (pintype "bidirectional"))
    )
    (net (code "65") (name "unconnected-(U$1-PIN13_N.C-PadPIN13)") (class "Default")
      (node (ref "U$1") (pin "PIN13") (pinfunction "PIN13_N.C_PIN13") (pintype "bidirectional"))
    )
    (net (code "66") (name "unconnected-(U$1-PIN37_N.C-PadPIN37)") (class "Default")
      (node (ref "U$1") (pin "PIN37") (pinfunction "PIN37_N.C_PIN37") (pintype "bidirectional"))
    )
    (net (code "67") (name "unconnected-(U$1-PIN47_N.C-PadPIN47)") (class "Default")
      (node (ref "U$1") (pin "PIN47") (pinfunction "PIN47_N.C_PIN47") (pintype "bidirectional"))
    )
    (net (code "68") (name "unconnected-(U$1-PIN48_N.C-PadPIN48)") (class "Default")
      (node (ref "U$1") (pin "PIN48") (pinfunction "PIN48_N.C_PIN48") (pintype "bidirectional"))
    )
    (net (code "69") (name "unconnected-(U$23-PadPIN2)") (class "Default")
      (node (ref "U$23") (pin "PIN2") (pinfunction "PIN2_PIN2") (pintype "bidirectional"))
    )
  )
)
